# CAN-Simulator_v2.net
KiCad netlist of a schematic drawn in EAGLE
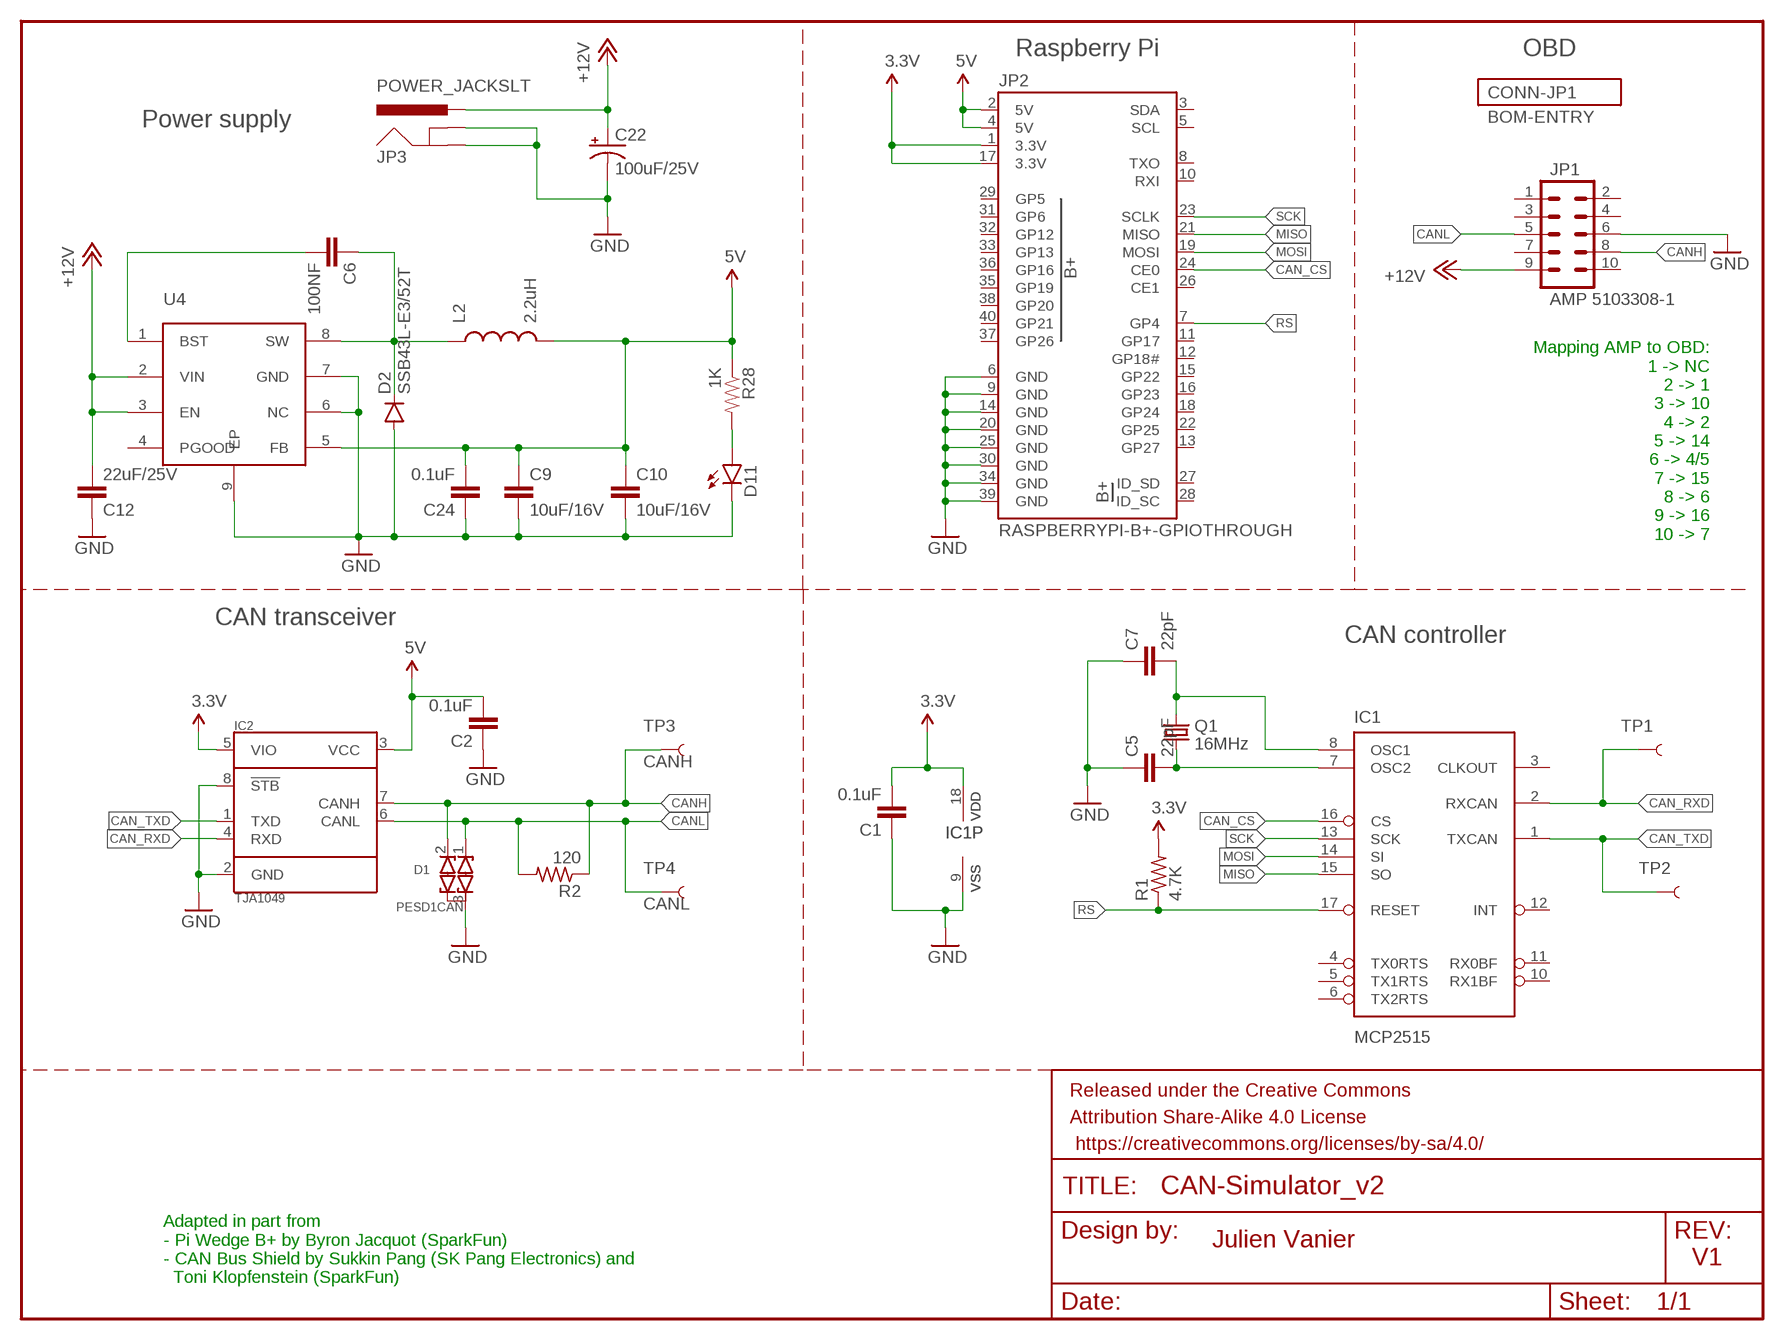
[diagram p0: schematic, sheet 1]

(export (version "E")
  (design (tool "Eeschema 10.0.6"))
  (components
    (comp (ref "C1")
      (value "0.1uF")
      (footprint "eagle-import:0402-CAP")
      (libsource (lib "eagle-import") (part "CAP0402-CAP"))
    )
    (comp (ref "C2")
      (value "0.1uF")
      (footprint "eagle-import:0402-CAP")
      (libsource (lib "eagle-import") (part "CAP0402-CAP"))
    )
    (comp (ref "C5")
      (value "22pF")
      (footprint "eagle-import:C0805")
      (fields (field (name "PARTNO") "C0805C220J5GACTU"))
      (libsource (lib "eagle-import") (part "C-EUC0805"))
    )
    (comp (ref "C6")
      (value "100NF")
      (footprint "eagle-import:0402-CAP")
      (libsource (lib "eagle-import") (part "CAP0402-CAP"))
    )
    (comp (ref "C7")
      (value "22pF")
      (footprint "eagle-import:C0805")
      (fields (field (name "PARTNO") "C0805C220J5GACTU"))
      (libsource (lib "eagle-import") (part "C-EUC0805"))
    )
    (comp (ref "C9")
      (value "10uF/16V")
      (footprint "eagle-import:0805-CAP")
      (libsource (lib "eagle-import") (part "10UF10V10%(0805)"))
    )
    (comp (ref "C10")
      (value "10uF/16V")
      (footprint "eagle-import:0805-CAP")
      (libsource (lib "eagle-import") (part "10UF10V10%(0805)"))
    )
    (comp (ref "C12")
      (value "22uF/25V")
      (footprint "eagle-import:1210")
      (libsource (lib "eagle-import") (part "22UF-16V-20%-(1210)"))
    )
    (comp (ref "C22")
      (value "100uF/25V")
      (footprint "eagle-import:CPOL-RADIAL-100UF-25V")
      (libsource (lib "eagle-import") (part "100UF-25V-20%(PTH)"))
    )
    (comp (ref "C24")
      (value "0.1uF")
      (footprint "eagle-import:0402-CAP")
      (libsource (lib "eagle-import") (part "CAP0402-CAP"))
    )
    (comp (ref "D1")
      (value "PESD1CAN")
      (footprint "eagle-import:SOT23")
      (fields (field (name "PARTNO") "PESD1CAN-215"))
      (libsource (lib "eagle-import") (part "DIODE_ESD_DUAL-SOT-23"))
    )
    (comp (ref "D2")
      (value "SSB43L-E3/52T")
      (footprint "eagle-import:SMB-DIODE")
      (libsource (lib "eagle-import") (part "DIODESMB"))
    )
    (comp (ref "D11")
      (value "LED0603")
      (footprint "eagle-import:LED-0603")
      (libsource (lib "eagle-import") (part "LED0603"))
    )
    (comp (ref "FRAME1")
      (value "FRAME-LETTER")
      (footprint "eagle-import:CREATIVE_COMMONS")
      (fields (field (name "BOM") "EXCLUDE"))
      (libsource (lib "eagle-import") (part "FRAME-LETTER"))
    )
    (comp (ref "IC1")
      (value "MCP2515")
      (footprint "eagle-import:SO-18W")
      (fields (field (name "PARTNO") "MCP2515-I/SO"))
      (libsource (lib "eagle-import") (part "MCP2510SO"))
    )
    (comp (ref "IC2")
      (value "TJA1049")
      (footprint "eagle-import:SO8")
      (fields (field (name "PARTNO") "TJA1049T-118"))
      (libsource (lib "eagle-import") (part "TJA1049"))
    )
    (comp (ref "JP1")
      (value "AMP 5103308-1")
      (footprint "eagle-import:2X5-SHROUDED")
      (fields (field (name "PARTNO") "5103308-1"))
      (libsource (lib "eagle-import") (part "M05X2SHD"))
    )
    (comp (ref "JP2")
      (value "RASPBERRYPI-B+-GPIOTHROUGH")
      (footprint "eagle-import:PIN_20X2")
      (libsource (lib "eagle-import") (part "RASPBERRYPI-B+-GPIOTHROUGH"))
    )
    (comp (ref "JP3")
      (value "POWER_JACKSLT")
      (footprint "eagle-import:POWER_JACK_SLOT")
      (libsource (lib "eagle-import") (part "POWER_JACKSLT"))
    )
    (comp (ref "L2")
      (value "2.2uH")
      (footprint "eagle-import:I4818")
      (libsource (lib "eagle-import") (part "INDUCTOR4818"))
    )
    (comp (ref "Q1")
      (value "16MHz")
      (footprint "eagle-import:CRYSTAL-SMD-5X3")
      (fields (field (name "PARTNO") "ABM3B-16.000MHZ-10-1-U-T"))
      (libsource (lib "eagle-import") (part "CRYSTAL5X3"))
    )
    (comp (ref "R1")
      (value "4.7K")
      (footprint "eagle-import:R0402")
      (fields (field (name "PARTNO") "RC0805JR-0747KL"))
      (libsource (lib "eagle-import") (part "R-US_R0402"))
    )
    (comp (ref "R2")
      (value "120")
      (footprint "eagle-import:R0603")
      (fields (field (name "PARTNO") "RC0603FR-07120RL"))
      (libsource (lib "eagle-import") (part "R-US_R0603"))
    )
    (comp (ref "R28")
      (value "1K")
      (footprint "eagle-import:0402-RES")
      (libsource (lib "eagle-import") (part "RESISTOR0402-RES"))
    )
    (comp (ref "TP1")
      (value "TEST-POINT3X5")
      (footprint "eagle-import:PAD.03X.05")
      (libsource (lib "eagle-import") (part "TEST-POINT3X5"))
    )
    (comp (ref "TP2")
      (value "TEST-POINT3X5")
      (footprint "eagle-import:PAD.03X.05")
      (libsource (lib "eagle-import") (part "TEST-POINT3X5"))
    )
    (comp (ref "TP3")
      (value "CANH")
      (footprint "eagle-import:PAD.03X.03")
      (libsource (lib "eagle-import") (part "TEST-POINT3"))
    )
    (comp (ref "TP4")
      (value "CANL")
      (footprint "eagle-import:PAD.03X.03")
      (libsource (lib "eagle-import") (part "TEST-POINT3"))
    )
    (comp (ref "U4")
      (value "ADP2303")
      (footprint "eagle-import:ADP2302")
      (libsource (lib "eagle-import") (part "ADP2303"))
    )
  )
  (nets
    (net (code "1") (name "+12V") (class "Default")
      (node (ref "C12") (pin "2") (pinfunction "2_2") (pintype "passive"))
      (node (ref "C22") (pin "1") (pinfunction "+_1") (pintype "passive"))
      (node (ref "JP1") (pin "9") (pinfunction "9_9") (pintype "passive"))
      (node (ref "JP3") (pin "PWR") (pinfunction "PWR_PWR") (pintype "bidirectional"))
      (node (ref "U4") (pin "2") (pinfunction "VIN_2") (pintype "bidirectional"))
      (node (ref "U4") (pin "3") (pinfunction "EN_3") (pintype "bidirectional"))
    )
    (net (code "2") (name "3.3V") (class "Default")
      (node (ref "C1") (pin "2") (pinfunction "2_2") (pintype "passive"))
      (node (ref "IC1") (pin "18") (pinfunction "VDD_18") (pintype "power_in"))
      (node (ref "IC2") (pin "5") (pinfunction "VIO_5") (pintype "bidirectional"))
      (node (ref "JP2") (pin "1") (pinfunction "3.3V_1") (pintype "power_in"))
      (node (ref "JP2") (pin "17") (pinfunction "3.3V_17") (pintype "power_in"))
      (node (ref "R1") (pin "2") (pinfunction "2_2") (pintype "passive"))
    )
    (net (code "3") (name "5V") (class "Default")
      (node (ref "C10") (pin "1") (pinfunction "1_1") (pintype "passive"))
      (node (ref "C2") (pin "2") (pinfunction "2_2") (pintype "passive"))
      (node (ref "C24") (pin "2") (pinfunction "2_2") (pintype "passive"))
      (node (ref "C9") (pin "1") (pinfunction "1_1") (pintype "passive"))
      (node (ref "IC2") (pin "3") (pinfunction "VCC_3") (pintype "bidirectional"))
      (node (ref "JP2") (pin "2") (pinfunction "5V_2") (pintype "power_in"))
      (node (ref "JP2") (pin "4") (pinfunction "5V_4") (pintype "power_in"))
      (node (ref "L2") (pin "2") (pinfunction "2_2") (pintype "passive"))
      (node (ref "R28") (pin "1") (pinfunction "1_1") (pintype "passive"))
      (node (ref "U4") (pin "5") (pinfunction "FB_5") (pintype "bidirectional"))
    )
    (net (code "4") (name "CANH") (class "Default")
      (node (ref "D1") (pin "2") (pinfunction "C2_2") (pintype "power_in"))
      (node (ref "IC2") (pin "7") (pinfunction "CANH_7") (pintype "bidirectional"))
      (node (ref "JP1") (pin "8") (pinfunction "8_8") (pintype "passive"))
      (node (ref "R2") (pin "1") (pinfunction "1_1") (pintype "passive"))
      (node (ref "TP3") (pin "P$1") (pinfunction "1_P$1") (pintype "bidirectional"))
    )
    (net (code "5") (name "CANL") (class "Default")
      (node (ref "D1") (pin "1") (pinfunction "C1_1") (pintype "power_in"))
      (node (ref "IC2") (pin "6") (pinfunction "CANL_6") (pintype "bidirectional"))
      (node (ref "JP1") (pin "5") (pinfunction "5_5") (pintype "passive"))
      (node (ref "R2") (pin "2") (pinfunction "2_2") (pintype "passive"))
      (node (ref "TP4") (pin "P$1") (pinfunction "1_P$1") (pintype "bidirectional"))
    )
    (net (code "6") (name "CAN_CS") (class "Default")
      (node (ref "IC1") (pin "16") (pinfunction "CS_16") (pintype "input"))
      (node (ref "JP2") (pin "24") (pinfunction "CE0_24") (pintype "output"))
    )
    (net (code "7") (name "CAN_RXD") (class "Default")
      (node (ref "IC1") (pin "2") (pinfunction "RXCAN_2") (pintype "input"))
      (node (ref "IC2") (pin "4") (pinfunction "RXD_4") (pintype "bidirectional"))
      (node (ref "TP1") (pin "P$1") (pinfunction "1_P$1") (pintype "bidirectional"))
    )
    (net (code "8") (name "CAN_TXD") (class "Default")
      (node (ref "IC1") (pin "1") (pinfunction "TXCAN_1") (pintype "output"))
      (node (ref "IC2") (pin "1") (pinfunction "TXD_1") (pintype "bidirectional"))
      (node (ref "TP2") (pin "P$1") (pinfunction "1_P$1") (pintype "bidirectional"))
    )
    (net (code "9") (name "GND") (class "Default")
      (node (ref "C1") (pin "1") (pinfunction "1_1") (pintype "passive"))
      (node (ref "C10") (pin "2") (pinfunction "2_2") (pintype "passive"))
      (node (ref "C12") (pin "1") (pinfunction "1_1") (pintype "passive"))
      (node (ref "C2") (pin "1") (pinfunction "1_1") (pintype "passive"))
      (node (ref "C22") (pin "2") (pinfunction "-_2") (pintype "passive"))
      (node (ref "C24") (pin "1") (pinfunction "1_1") (pintype "passive"))
      (node (ref "C5") (pin "1") (pinfunction "1_1") (pintype "passive"))
      (node (ref "C7") (pin "1") (pinfunction "1_1") (pintype "passive"))
      (node (ref "C9") (pin "2") (pinfunction "2_2") (pintype "passive"))
      (node (ref "D1") (pin "3") (pinfunction "COM_3") (pintype "power_in"))
      (node (ref "D11") (pin "C") (pinfunction "C_C") (pintype "passive"))
      (node (ref "D2") (pin "A") (pinfunction "A_A") (pintype "passive"))
      (node (ref "IC1") (pin "9") (pinfunction "VSS_9") (pintype "power_in"))
      (node (ref "IC2") (pin "2") (pinfunction "GND_2") (pintype "bidirectional"))
      (node (ref "IC2") (pin "8") (pinfunction "~{STB}_8") (pintype "bidirectional"))
      (node (ref "JP1") (pin "6") (pinfunction "6_6") (pintype "passive"))
      (node (ref "JP2") (pin "14") (pinfunction "GND_14") (pintype "power_in"))
      (node (ref "JP2") (pin "20") (pinfunction "GND_20") (pintype "power_in"))
      (node (ref "JP2") (pin "25") (pinfunction "GND_25") (pintype "power_in"))
      (node (ref "JP2") (pin "30") (pinfunction "GND_30") (pintype "power_in"))
      (node (ref "JP2") (pin "34") (pinfunction "GND_34") (pintype "power_in"))
      (node (ref "JP2") (pin "39") (pinfunction "GND_39") (pintype "power_in"))
      (node (ref "JP2") (pin "6") (pinfunction "GND_6") (pintype "power_in"))
      (node (ref "JP2") (pin "9") (pinfunction "GND_9") (pintype "power_in"))
      (node (ref "JP3") (pin "GND@1") (pinfunction "GNDBREAK_GND@1") (pintype "bidirectional"))
      (node (ref "JP3") (pin "GND@2") (pinfunction "GND_GND@2") (pintype "bidirectional"))
      (node (ref "U4") (pin "6") (pinfunction "NC_6") (pintype "bidirectional"))
      (node (ref "U4") (pin "7") (pinfunction "GND_7") (pintype "bidirectional"))
      (node (ref "U4") (pin "9") (pinfunction "EP_9") (pintype "bidirectional"))
    )
    (net (code "10") (name "MISO") (class "Default")
      (node (ref "IC1") (pin "15") (pinfunction "SO_15") (pintype "output"))
      (node (ref "JP2") (pin "21") (pinfunction "MISO_21") (pintype "input"))
    )
    (net (code "11") (name "MOSI") (class "Default")
      (node (ref "IC1") (pin "14") (pinfunction "SI_14") (pintype "input"))
      (node (ref "JP2") (pin "19") (pinfunction "MOSI_19") (pintype "output"))
    )
    (net (code "12") (name "Net-(D11-PadA)") (class "Default")
      (node (ref "D11") (pin "A") (pinfunction "A_A") (pintype "passive"))
      (node (ref "R28") (pin "2") (pinfunction "2_2") (pintype "passive"))
    )
    (net (code "13") (name "Net-(IC1A-OSC1)") (class "Default")
      (node (ref "C7") (pin "2") (pinfunction "2_2") (pintype "passive"))
      (node (ref "IC1") (pin "8") (pinfunction "OSC1_8") (pintype "input"))
      (node (ref "Q1") (pin "3") (pinfunction "2_3") (pintype "passive"))
    )
    (net (code "14") (name "Net-(IC1A-OSC2)") (class "Default")
      (node (ref "C5") (pin "2") (pinfunction "2_2") (pintype "passive"))
      (node (ref "IC1") (pin "7") (pinfunction "OSC2_7") (pintype "output"))
      (node (ref "Q1") (pin "1") (pinfunction "1_1") (pintype "passive"))
    )
    (net (code "15") (name "Net-(U4-BST)") (class "Default")
      (node (ref "C6") (pin "2") (pinfunction "2_2") (pintype "passive"))
      (node (ref "U4") (pin "1") (pinfunction "BST_1") (pintype "bidirectional"))
    )
    (net (code "16") (name "Net-(U4-SW)") (class "Default")
      (node (ref "C6") (pin "1") (pinfunction "1_1") (pintype "passive"))
      (node (ref "D2") (pin "C") (pinfunction "C_C") (pintype "passive"))
      (node (ref "L2") (pin "1") (pinfunction "1_1") (pintype "passive"))
      (node (ref "U4") (pin "8") (pinfunction "SW_8") (pintype "bidirectional"))
    )
    (net (code "17") (name "RS") (class "Default")
      (node (ref "IC1") (pin "17") (pinfunction "RESET_17") (pintype "input"))
      (node (ref "JP2") (pin "7") (pinfunction "GP4_7") (pintype "bidirectional"))
      (node (ref "R1") (pin "1") (pinfunction "1_1") (pintype "passive"))
    )
    (net (code "18") (name "SCK") (class "Default")
      (node (ref "IC1") (pin "13") (pinfunction "SCK_13") (pintype "input"))
      (node (ref "JP2") (pin "23") (pinfunction "SCLK_23") (pintype "output"))
    )
    (net (code "19") (name "unconnected-(IC1A-CLKOUT-Pad3)") (class "Default")
      (node (ref "IC1") (pin "3") (pinfunction "CLKOUT_3") (pintype "output"))
    )
    (net (code "20") (name "unconnected-(IC1A-INT-Pad12)") (class "Default")
      (node (ref "IC1") (pin "12") (pinfunction "INT_12") (pintype "output"))
    )
    (net (code "21") (name "unconnected-(IC1A-RX0BF-Pad11)") (class "Default")
      (node (ref "IC1") (pin "11") (pinfunction "RX0BF_11") (pintype "output"))
    )
    (net (code "22") (name "unconnected-(IC1A-RX1BF-Pad10)") (class "Default")
      (node (ref "IC1") (pin "10") (pinfunction "RX1BF_10") (pintype "output"))
    )
    (net (code "23") (name "unconnected-(IC1A-TX0RTS-Pad4)") (class "Default")
      (node (ref "IC1") (pin "4") (pinfunction "TX0RTS_4") (pintype "input"))
    )
    (net (code "24") (name "unconnected-(IC1A-TX1RTS-Pad5)") (class "Default")
      (node (ref "IC1") (pin "5") (pinfunction "TX1RTS_5") (pintype "input"))
    )
    (net (code "25") (name "unconnected-(IC1A-TX2RTS-Pad6)") (class "Default")
      (node (ref "IC1") (pin "6") (pinfunction "TX2RTS_6") (pintype "input"))
    )
    (net (code "26") (name "unconnected-(JP1-Pad1)") (class "Default")
      (node (ref "JP1") (pin "1") (pinfunction "1_1") (pintype "passive"))
    )
    (net (code "27") (name "unconnected-(JP1-Pad2)") (class "Default")
      (node (ref "JP1") (pin "2") (pinfunction "2_2") (pintype "passive"))
    )
    (net (code "28") (name "unconnected-(JP1-Pad3)") (class "Default")
      (node (ref "JP1") (pin "3") (pinfunction "3_3") (pintype "passive"))
    )
    (net (code "29") (name "unconnected-(JP1-Pad4)") (class "Default")
      (node (ref "JP1") (pin "4") (pinfunction "4_4") (pintype "passive"))
    )
    (net (code "30") (name "unconnected-(JP1-Pad7)") (class "Default")
      (node (ref "JP1") (pin "7") (pinfunction "7_7") (pintype "passive"))
    )
    (net (code "31") (name "unconnected-(JP1-Pad10)") (class "Default")
      (node (ref "JP1") (pin "10") (pinfunction "10_10") (pintype "passive"))
    )
    (net (code "32") (name "unconnected-(JP2-CE1-Pad26)") (class "Default")
      (node (ref "JP2") (pin "26") (pinfunction "CE1_26") (pintype "output"))
    )
    (net (code "33") (name "unconnected-(JP2-GP5-Pad29)") (class "Default")
      (node (ref "JP2") (pin "29") (pinfunction "GP5_29") (pintype "bidirectional"))
    )
    (net (code "34") (name "unconnected-(JP2-GP6-Pad31)") (class "Default")
      (node (ref "JP2") (pin "31") (pinfunction "GP6_31") (pintype "bidirectional"))
    )
    (net (code "35") (name "unconnected-(JP2-GP12-Pad32)") (class "Default")
      (node (ref "JP2") (pin "32") (pinfunction "GP12_32") (pintype "bidirectional"))
    )
    (net (code "36") (name "unconnected-(JP2-GP13-Pad33)") (class "Default")
      (node (ref "JP2") (pin "33") (pinfunction "GP13_33") (pintype "bidirectional"))
    )
    (net (code "37") (name "unconnected-(JP2-GP16-Pad36)") (class "Default")
      (node (ref "JP2") (pin "36") (pinfunction "GP16_36") (pintype "bidirectional"))
    )
    (net (code "38") (name "unconnected-(JP2-GP17-Pad11)") (class "Default")
      (node (ref "JP2") (pin "11") (pinfunction "GP17_11") (pintype "bidirectional"))
    )
    (net (code "39") (name "unconnected-(JP2-GP18#-Pad12)") (class "Default")
      (node (ref "JP2") (pin "12") (pinfunction "GP18#_12") (pintype "bidirectional"))
    )
    (net (code "40") (name "unconnected-(JP2-GP19-Pad35)") (class "Default")
      (node (ref "JP2") (pin "35") (pinfunction "GP19_35") (pintype "bidirectional"))
    )
    (net (code "41") (name "unconnected-(JP2-GP20-Pad38)") (class "Default")
      (node (ref "JP2") (pin "38") (pinfunction "GP20_38") (pintype "bidirectional"))
    )
    (net (code "42") (name "unconnected-(JP2-GP21-Pad40)") (class "Default")
      (node (ref "JP2") (pin "40") (pinfunction "GP21_40") (pintype "bidirectional"))
    )
    (net (code "43") (name "unconnected-(JP2-GP22-Pad15)") (class "Default")
      (node (ref "JP2") (pin "15") (pinfunction "GP22_15") (pintype "bidirectional"))
    )
    (net (code "44") (name "unconnected-(JP2-GP23-Pad16)") (class "Default")
      (node (ref "JP2") (pin "16") (pinfunction "GP23_16") (pintype "bidirectional"))
    )
    (net (code "45") (name "unconnected-(JP2-GP24-Pad18)") (class "Default")
      (node (ref "JP2") (pin "18") (pinfunction "GP24_18") (pintype "bidirectional"))
    )
    (net (code "46") (name "unconnected-(JP2-GP25-Pad22)") (class "Default")
      (node (ref "JP2") (pin "22") (pinfunction "GP25_22") (pintype "bidirectional"))
    )
    (net (code "47") (name "unconnected-(JP2-GP26-Pad37)") (class "Default")
      (node (ref "JP2") (pin "37") (pinfunction "GP26_37") (pintype "bidirectional"))
    )
    (net (code "48") (name "unconnected-(JP2-GP27-Pad13)") (class "Default")
      (node (ref "JP2") (pin "13") (pinfunction "GP27_13") (pintype "bidirectional"))
    )
    (net (code "49") (name "unconnected-(JP2-ID_SC-Pad28)") (class "Default")
      (node (ref "JP2") (pin "28") (pinfunction "ID_SC_28") (pintype "bidirectional"))
    )
    (net (code "50") (name "unconnected-(JP2-ID_SD-Pad27)") (class "Default")
      (node (ref "JP2") (pin "27") (pinfunction "ID_SD_27") (pintype "bidirectional"))
    )
    (net (code "51") (name "unconnected-(JP2-RXI-Pad10)") (class "Default")
      (node (ref "JP2") (pin "10") (pinfunction "RXI_10") (pintype "input"))
    )
    (net (code "52") (name "unconnected-(JP2-SCL-Pad5)") (class "Default")
      (node (ref "JP2") (pin "5") (pinfunction "SCL_5") (pintype "bidirectional"))
    )
    (net (code "53") (name "unconnected-(JP2-SDA-Pad3)") (class "Default")
      (node (ref "JP2") (pin "3") (pinfunction "SDA_3") (pintype "bidirectional"))
    )
    (net (code "54") (name "unconnected-(JP2-TXO-Pad8)") (class "Default")
      (node (ref "JP2") (pin "8") (pinfunction "TXO_8") (pintype "output"))
    )
    (net (code "55") (name "unconnected-(U4-PGOOD-Pad4)") (class "Default")
      (node (ref "U4") (pin "4") (pinfunction "PGOOD_4") (pintype "bidirectional"))
    )
  )
)
